# PWM_inverter.net
KiCad netlist of a schematic drawn in Altium Designer
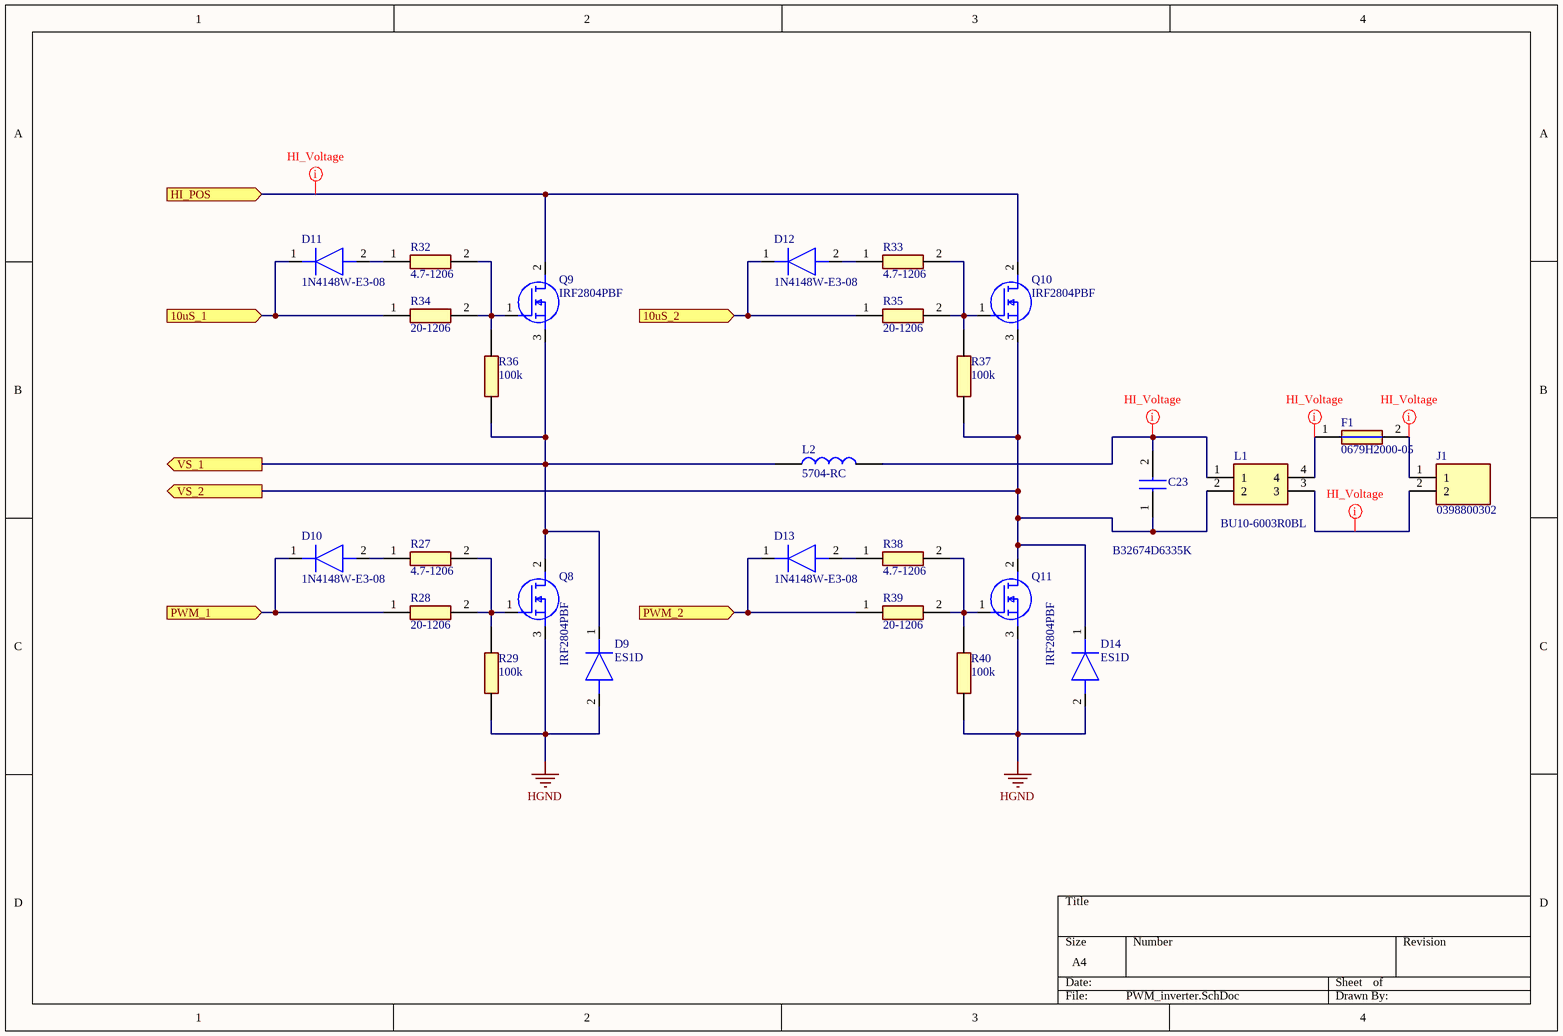
[diagram p0: PWM_inverter.SchDoc]

(export (version "E")
  (design (tool "Eeschema 10.0.6"))
  (components
    (comp (ref "C23")
      (value "B32674D6335K")
      (footprint "B32674D6335K")
      (description "Capacitor")
      (fields (field (name "MOUSER PART NUMBER") "871-B32674D6335K"))
      (libsource (lib "SamacSys") (part "B32674D6335K"))
    )
    (comp (ref "D9")
      (value "ES1D")
      (footprint "SamacSys:DIOM5226X295N")
      (description "Diode")
      (libsource (lib "SamacSys") (part "ES1D"))
    )
    (comp (ref "D10")
      (value "1N4148W-E3-08")
      (footprint "SamacSys:SOD3716X135N")
      (description "Diode")
      (fields (field (name "MOUSER PART NUMBER") "78-1N4148W-E3-08"))
      (libsource (lib "*") (part "1N4148W-E3-08"))
    )
    (comp (ref "D11")
      (value "1N4148W-E3-08")
      (footprint "SamacSys:SOD3716X135N")
      (description "Diode")
      (fields (field (name "MOUSER PART NUMBER") "78-1N4148W-E3-08"))
      (libsource (lib "*") (part "1N4148W-E3-08"))
    )
    (comp (ref "D12")
      (value "1N4148W-E3-08")
      (footprint "SamacSys:SOD3716X135N")
      (description "Diode")
      (fields (field (name "MOUSER PART NUMBER") "78-1N4148W-E3-08"))
      (libsource (lib "*") (part "1N4148W-E3-08"))
    )
    (comp (ref "D13")
      (value "1N4148W-E3-08")
      (footprint "SamacSys:SOD3716X135N")
      (description "Diode")
      (fields (field (name "MOUSER PART NUMBER") "78-1N4148W-E3-08"))
      (libsource (lib "*") (part "1N4148W-E3-08"))
    )
    (comp (ref "D14")
      (value "ES1D")
      (footprint "SamacSys:DIOM5226X295N")
      (description "Diode")
      (libsource (lib "SamacSys") (part "ES1D"))
    )
    (comp (ref "F1")
      (value "0679H2000-05")
      (footprint "SamacSys:FUSC6125X279N")
      (description "Fuse")
      (libsource (lib "*") (part "0679H2000-05"))
    )
    (comp (ref "J1")
      (value "0398800302")
      (footprint "SamacSys:0398800302")
      (description "Connector")
      (libsource (lib "*") (part "0398800302"))
    )
    (comp (ref "L1")
      (value "BU10-6003R0BL")
      (footprint "SamacSys:BU106003R0BL")
      (description "Inductor")
      (fields (field (name "MOUSER PART NUMBER") "994-BU10-6003R0BL"))
      (libsource (lib "*") (part "BU10-6003R0BL"))
    )
    (comp (ref "L2")
      (value "5704-RC")
      (footprint "5704RC")
      (description "Inductor High Current Toroid 275uH/150uH 15% 1KHz 2A 0.24Ohm DCR RDL")
      (fields (field (name "MOUSER PART NUMBER") "542-5704-RC"))
      (libsource (lib "5704-RC") (part "5704-RC"))
    )
    (comp (ref "Q8")
      (value "IRF2804PBF")
      (footprint "SamacSys:TO254P482X1016X2192-3P")
      (description "MOSFET (N-Channel)")
      (fields (field (name "MOUSER PART NUMBER") "942-IRF2804PBF"))
      (libsource (lib "*") (part "IRF2804PBF"))
    )
    (comp (ref "Q9")
      (value "IRF2804PBF")
      (footprint "SamacSys:TO254P482X1016X2192-3P")
      (description "MOSFET (N-Channel)")
      (fields (field (name "MOUSER PART NUMBER") "942-IRF2804PBF"))
      (libsource (lib "*") (part "IRF2804PBF"))
    )
    (comp (ref "Q10")
      (value "IRF2804PBF")
      (footprint "SamacSys:TO254P482X1016X2192-3P")
      (description "MOSFET (N-Channel)")
      (fields (field (name "MOUSER PART NUMBER") "942-IRF2804PBF"))
      (libsource (lib "*") (part "IRF2804PBF"))
    )
    (comp (ref "Q11")
      (value "IRF2804PBF")
      (footprint "SamacSys:TO254P482X1016X2192-3P")
      (description "MOSFET (N-Channel)")
      (fields (field (name "MOUSER PART NUMBER") "942-IRF2804PBF"))
      (libsource (lib "*") (part "IRF2804PBF"))
    )
    (comp (ref "R27")
      (value "4.7-1206")
      (footprint "SamacSys:RESC3116X75N")
      (description "Resistor")
      (libsource (lib "*") (part "MCMR12X1003FTL"))
    )
    (comp (ref "R28")
      (value "20-1206")
      (footprint "SamacSys:RESC3116X75N")
      (description "Resistor")
      (libsource (lib "*") (part "MCMR12X1003FTL"))
    )
    (comp (ref "R29")
      (value "100k")
      (footprint "RESC2013X65N")
      (description "Resistor")
      (libsource (lib "SamacSys") (part "ERJP06J822V"))
    )
    (comp (ref "R32")
      (value "4.7-1206")
      (footprint "SamacSys:RESC3116X75N")
      (description "Resistor")
      (libsource (lib "*") (part "MCMR12X1003FTL"))
    )
    (comp (ref "R33")
      (value "4.7-1206")
      (footprint "SamacSys:RESC3116X75N")
      (description "Resistor")
      (libsource (lib "*") (part "MCMR12X1003FTL"))
    )
    (comp (ref "R34")
      (value "20-1206")
      (footprint "SamacSys:RESC3116X75N")
      (description "Resistor")
      (libsource (lib "*") (part "MCMR12X1003FTL"))
    )
    (comp (ref "R35")
      (value "20-1206")
      (footprint "SamacSys:RESC3116X75N")
      (description "Resistor")
      (libsource (lib "*") (part "MCMR12X1003FTL"))
    )
    (comp (ref "R36")
      (value "100k")
      (footprint "RESC2013X65N")
      (description "Resistor")
      (libsource (lib "SamacSys") (part "ERJP06J822V"))
    )
    (comp (ref "R37")
      (value "100k")
      (footprint "RESC2013X65N")
      (description "Resistor")
      (libsource (lib "SamacSys") (part "ERJP06J822V"))
    )
    (comp (ref "R38")
      (value "4.7-1206")
      (footprint "SamacSys:RESC3116X75N")
      (description "Resistor")
      (libsource (lib "*") (part "MCMR12X1003FTL"))
    )
    (comp (ref "R39")
      (value "20-1206")
      (footprint "SamacSys:RESC3116X75N")
      (description "Resistor")
      (libsource (lib "*") (part "MCMR12X1003FTL"))
    )
    (comp (ref "R40")
      (value "100k")
      (footprint "RESC2013X65N")
      (description "Resistor")
      (libsource (lib "SamacSys") (part "ERJP06J822V"))
    )
  )
  (nets
    (net (code "1") (name "/10uS_1") (class "Default")
      (node (ref "D11") (pin "1") (pinfunction "K_1") (pintype "passive"))
      (node (ref "R34") (pin "1") (pinfunction "1_1") (pintype "passive"))
    )
    (net (code "2") (name "/10uS_2") (class "Default")
      (node (ref "D12") (pin "1") (pinfunction "K_1") (pintype "passive"))
      (node (ref "R35") (pin "1") (pinfunction "1_1") (pintype "passive"))
    )
    (net (code "3") (name "/HI_POS") (class "Default")
      (node (ref "Q10") (pin "2") (pinfunction "D_2") (pintype "passive"))
      (node (ref "Q9") (pin "2") (pinfunction "D_2") (pintype "passive"))
    )
    (net (code "4") (name "/PWM_1") (class "Default")
      (node (ref "D10") (pin "1") (pinfunction "K_1") (pintype "passive"))
      (node (ref "R28") (pin "1") (pinfunction "1_1") (pintype "passive"))
    )
    (net (code "5") (name "/PWM_2") (class "Default")
      (node (ref "D13") (pin "1") (pinfunction "K_1") (pintype "passive"))
      (node (ref "R39") (pin "1") (pinfunction "1_1") (pintype "passive"))
    )
    (net (code "6") (name "/VS_1") (class "Default")
      (node (ref "D9") (pin "1") (pinfunction "K_1") (pintype "passive"))
      (node (ref "L2") (pin "1") (pinfunction "1_1") (pintype "passive"))
      (node (ref "Q8") (pin "2") (pinfunction "D_2") (pintype "passive"))
      (node (ref "Q9") (pin "3") (pinfunction "S_3") (pintype "passive"))
      (node (ref "R36") (pin "1") (pinfunction "1_1") (pintype "passive"))
    )
    (net (code "7") (name "/VS_2") (class "Default")
      (node (ref "C23") (pin "1") (pinfunction "1_1") (pintype "passive"))
      (node (ref "D14") (pin "1") (pinfunction "K_1") (pintype "passive"))
      (node (ref "L1") (pin "2") (pinfunction "2_2") (pintype "passive"))
      (node (ref "Q10") (pin "3") (pinfunction "S_3") (pintype "passive"))
      (node (ref "Q11") (pin "2") (pinfunction "D_2") (pintype "passive"))
      (node (ref "R37") (pin "1") (pinfunction "1_1") (pintype "passive"))
    )
    (net (code "8") (name "HGND") (class "Default")
      (node (ref "D14") (pin "2") (pinfunction "A_2") (pintype "passive"))
      (node (ref "D9") (pin "2") (pinfunction "A_2") (pintype "passive"))
      (node (ref "Q11") (pin "3") (pinfunction "S_3") (pintype "passive"))
      (node (ref "Q8") (pin "3") (pinfunction "S_3") (pintype "passive"))
      (node (ref "R29") (pin "1") (pinfunction "1_1") (pintype "passive"))
      (node (ref "R40") (pin "1") (pinfunction "1_1") (pintype "passive"))
    )
    (net (code "9") (name "Net-(C23-Pad2)") (class "Default")
      (node (ref "C23") (pin "2") (pinfunction "2_2") (pintype "passive"))
      (node (ref "L1") (pin "1") (pinfunction "1_1") (pintype "passive"))
      (node (ref "L2") (pin "2") (pinfunction "2_2") (pintype "passive"))
    )
    (net (code "10") (name "Net-(D10-A)") (class "Default")
      (node (ref "D10") (pin "2") (pinfunction "A_2") (pintype "passive"))
      (node (ref "R27") (pin "1") (pinfunction "1_1") (pintype "passive"))
    )
    (net (code "11") (name "Net-(D11-A)") (class "Default")
      (node (ref "D11") (pin "2") (pinfunction "A_2") (pintype "passive"))
      (node (ref "R32") (pin "1") (pinfunction "1_1") (pintype "passive"))
    )
    (net (code "12") (name "Net-(D12-A)") (class "Default")
      (node (ref "D12") (pin "2") (pinfunction "A_2") (pintype "passive"))
      (node (ref "R33") (pin "1") (pinfunction "1_1") (pintype "passive"))
    )
    (net (code "13") (name "Net-(D13-A)") (class "Default")
      (node (ref "D13") (pin "2") (pinfunction "A_2") (pintype "passive"))
      (node (ref "R38") (pin "1") (pinfunction "1_1") (pintype "passive"))
    )
    (net (code "14") (name "Net-(F1-Pad1)") (class "Default")
      (node (ref "F1") (pin "1") (pinfunction "1_1") (pintype "passive"))
      (node (ref "L1") (pin "4") (pinfunction "4_4") (pintype "passive"))
    )
    (net (code "15") (name "Net-(F1-Pad2)") (class "Default")
      (node (ref "F1") (pin "2") (pinfunction "2_2") (pintype "passive"))
      (node (ref "J1") (pin "1") (pinfunction "1_1") (pintype "passive"))
    )
    (net (code "16") (name "Net-(J1-Pad2)") (class "Default")
      (node (ref "J1") (pin "2") (pinfunction "2_2") (pintype "passive"))
      (node (ref "L1") (pin "3") (pinfunction "3_3") (pintype "passive"))
    )
    (net (code "17") (name "Net-(Q8-G)") (class "Default")
      (node (ref "Q8") (pin "1") (pinfunction "G_1") (pintype "passive"))
      (node (ref "R27") (pin "2") (pinfunction "2_2") (pintype "passive"))
      (node (ref "R28") (pin "2") (pinfunction "2_2") (pintype "passive"))
      (node (ref "R29") (pin "2") (pinfunction "2_2") (pintype "passive"))
    )
    (net (code "18") (name "Net-(Q9-G)") (class "Default")
      (node (ref "Q9") (pin "1") (pinfunction "G_1") (pintype "passive"))
      (node (ref "R32") (pin "2") (pinfunction "2_2") (pintype "passive"))
      (node (ref "R34") (pin "2") (pinfunction "2_2") (pintype "passive"))
      (node (ref "R36") (pin "2") (pinfunction "2_2") (pintype "passive"))
    )
    (net (code "19") (name "Net-(Q10-G)") (class "Default")
      (node (ref "Q10") (pin "1") (pinfunction "G_1") (pintype "passive"))
      (node (ref "R33") (pin "2") (pinfunction "2_2") (pintype "passive"))
      (node (ref "R35") (pin "2") (pinfunction "2_2") (pintype "passive"))
      (node (ref "R37") (pin "2") (pinfunction "2_2") (pintype "passive"))
    )
    (net (code "20") (name "Net-(Q11-G)") (class "Default")
      (node (ref "Q11") (pin "1") (pinfunction "G_1") (pintype "passive"))
      (node (ref "R38") (pin "2") (pinfunction "2_2") (pintype "passive"))
      (node (ref "R39") (pin "2") (pinfunction "2_2") (pintype "passive"))
      (node (ref "R40") (pin "2") (pinfunction "2_2") (pintype "passive"))
    )
  )
)
